# Input_Board.net
KiCad netlist of a schematic drawn in EAGLE
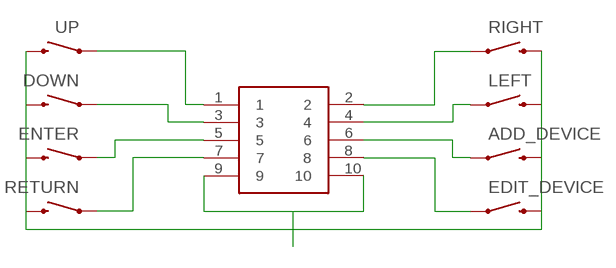
[diagram p0: schematic, sheet 1]

(export (version "E")
  (design (tool "Eeschema 10.0.6"))
  (components
    (comp (ref "ADD_DEVICE")
      (value "SWITCH-MOMENTARY-212MM")
      (footprint "eagle-import:TACTILE-PTH-12MM")
      (libsource (lib "eagle-import") (part "SWITCH-MOMENTARY-212MM"))
    )
    (comp (ref "DOWN")
      (value "SWITCH-MOMENTARY-212MM")
      (footprint "eagle-import:TACTILE-PTH-12MM")
      (libsource (lib "eagle-import") (part "SWITCH-MOMENTARY-212MM"))
    )
    (comp (ref "EDIT_DEVICE")
      (value "SWITCH-MOMENTARY-212MM")
      (footprint "eagle-import:TACTILE-PTH-12MM")
      (libsource (lib "eagle-import") (part "SWITCH-MOMENTARY-212MM"))
    )
    (comp (ref "ENTER")
      (value "SWITCH-MOMENTARY-212MM")
      (footprint "eagle-import:TACTILE-PTH-12MM")
      (libsource (lib "eagle-import") (part "SWITCH-MOMENTARY-212MM"))
    )
    (comp (ref "LEFT")
      (value "SWITCH-MOMENTARY-212MM")
      (footprint "eagle-import:TACTILE-PTH-12MM")
      (libsource (lib "eagle-import") (part "SWITCH-MOMENTARY-212MM"))
    )
    (comp (ref "RETURN")
      (value "SWITCH-MOMENTARY-212MM")
      (footprint "eagle-import:TACTILE-PTH-12MM")
      (libsource (lib "eagle-import") (part "SWITCH-MOMENTARY-212MM"))
    )
    (comp (ref "RIGHT")
      (value "SWITCH-MOMENTARY-212MM")
      (footprint "eagle-import:TACTILE-PTH-12MM")
      (libsource (lib "eagle-import") (part "SWITCH-MOMENTARY-212MM"))
    )
    (comp (ref "U$1")
      (value "10PIN_HEADER_MALE_SMD")
      (footprint "eagle-import:2X5-SHROUDED_SMD_BOTTOM")
      (libsource (lib "eagle-import") (part "10PIN_HEADER_MALE_SMD"))
    )
    (comp (ref "UP")
      (value "SWITCH-MOMENTARY-212MM")
      (footprint "eagle-import:TACTILE-PTH-12MM")
      (libsource (lib "eagle-import") (part "SWITCH-MOMENTARY-212MM"))
    )
  )
  (nets
    (net (code "1") (name "Net-(ADD_DEVICE-2)") (class "Default")
      (node (ref "ADD_DEVICE") (pin "3") (pinfunction "2_3") (pintype "passive"))
      (node (ref "DOWN") (pin "3") (pinfunction "2_3") (pintype "passive"))
      (node (ref "EDIT_DEVICE") (pin "3") (pinfunction "2_3") (pintype "passive"))
      (node (ref "ENTER") (pin "3") (pinfunction "2_3") (pintype "passive"))
      (node (ref "LEFT") (pin "3") (pinfunction "2_3") (pintype "passive"))
      (node (ref "RETURN") (pin "3") (pinfunction "2_3") (pintype "passive"))
      (node (ref "RIGHT") (pin "3") (pinfunction "2_3") (pintype "passive"))
      (node (ref "U$1") (pin "10") (pinfunction "10_10") (pintype "bidirectional"))
      (node (ref "U$1") (pin "9") (pinfunction "9_9") (pintype "bidirectional"))
      (node (ref "UP") (pin "3") (pinfunction "2_3") (pintype "passive"))
    )
    (net (code "2") (name "Net-(ADD_DEVICE-Pad1)") (class "Default")
      (node (ref "ADD_DEVICE") (pin "1") (pinfunction "1_1") (pintype "passive"))
      (node (ref "U$1") (pin "6") (pinfunction "6_6") (pintype "bidirectional"))
    )
    (net (code "3") (name "Net-(DOWN-Pad1)") (class "Default")
      (node (ref "DOWN") (pin "1") (pinfunction "1_1") (pintype "passive"))
      (node (ref "U$1") (pin "3") (pinfunction "3_3") (pintype "bidirectional"))
    )
    (net (code "4") (name "Net-(EDIT_DEVICE-Pad1)") (class "Default")
      (node (ref "EDIT_DEVICE") (pin "1") (pinfunction "1_1") (pintype "passive"))
      (node (ref "U$1") (pin "8") (pinfunction "8_8") (pintype "bidirectional"))
    )
    (net (code "5") (name "Net-(ENTER-Pad1)") (class "Default")
      (node (ref "ENTER") (pin "1") (pinfunction "1_1") (pintype "passive"))
      (node (ref "U$1") (pin "5") (pinfunction "5_5") (pintype "bidirectional"))
    )
    (net (code "6") (name "Net-(LEFT-Pad1)") (class "Default")
      (node (ref "LEFT") (pin "1") (pinfunction "1_1") (pintype "passive"))
      (node (ref "U$1") (pin "4") (pinfunction "4_4") (pintype "bidirectional"))
    )
    (net (code "7") (name "Net-(RETURN-Pad1)") (class "Default")
      (node (ref "RETURN") (pin "1") (pinfunction "1_1") (pintype "passive"))
      (node (ref "U$1") (pin "7") (pinfunction "7_7") (pintype "bidirectional"))
    )
    (net (code "8") (name "Net-(RIGHT-Pad1)") (class "Default")
      (node (ref "RIGHT") (pin "1") (pinfunction "1_1") (pintype "passive"))
      (node (ref "U$1") (pin "2") (pinfunction "2_2") (pintype "bidirectional"))
    )
    (net (code "9") (name "Net-(U$1-Pad1)") (class "Default")
      (node (ref "U$1") (pin "1") (pinfunction "1_1") (pintype "bidirectional"))
      (node (ref "UP") (pin "1") (pinfunction "1_1") (pintype "passive"))
    )
  )
)
